# RF_Module_ASK_Transfer.net
KiCad netlist of a schematic drawn in Altium Designer
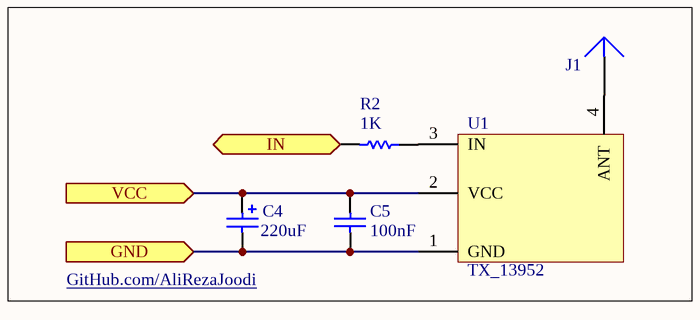
[diagram p0: RF Module_ASK_Transfer.SchDoc]

(export (version "E")
  (design (tool "Eeschema 10.0.6"))
  (components
    (comp (ref "C4")
      (value "220uF")
      (footprint "CAPPR3.05-3.81x6.35")
      (description "Polarized Capacitor (Radial)")
      (fields (field (name "MANUFACTURER") "Generic Components") (field (name "PUBLISHER") "Altium Limited"))
      (libsource (lib "Miscellaneous Devices") (part "Cap Pol1"))
    )
    (comp (ref "C5")
      (value "100nF")
      (footprint "CAPNTO2.54-3.05x1.78A")
      (description "Capacitor")
      (fields (field (name "MANUFACTURER") "Generic Components") (field (name "PUBLISHER") "Altium Limited"))
      (libsource (lib "Miscellaneous Devices") (part "Cap"))
    )
    (comp (ref "J1")
      (value "COAX-M")
      (footprint "PIN1")
      (description "Coax-M Connector")
      (fields (field (name "MANUFACTURER") "Generic Components") (field (name "PUBLISHER") "Altium Limited"))
      (libsource (lib "Miscellaneous Connectors") (part "COAX-M"))
    )
    (comp (ref "R2")
      (value "1K")
      (footprint "AXIAL-0.4")
      (description "Resistor")
      (fields (field (name "PUBLISHER") "Altium Limited"))
      (libsource (lib "Miscellaneous Devices") (part "Res1"))
    )
    (comp (ref "U1")
      (value "TX_13952")
      (footprint "RF_ASK_TX_13952")
      (description "Voltage Regulator")
      (fields (field (name "MANUFACTURER") "Generic Components") (field (name "PUBLISHER") "Altium Limited"))
      (libsource (lib "my Libraries") (part "RF_ASK_TX_13952_2"))
    )
  )
  (nets
    (net (code "1") (name "/GND") (class "Default")
      (node (ref "C4") (pin "2") (pinfunction "2_2") (pintype "passive"))
      (node (ref "C5") (pin "1") (pinfunction "1_1") (pintype "passive"))
      (node (ref "U1") (pin "1") (pinfunction "GND_1") (pintype "passive"))
    )
    (net (code "2") (name "/IN") (class "Default")
      (node (ref "R2") (pin "2") (pinfunction "2_2") (pintype "passive"))
    )
    (net (code "3") (name "/VCC") (class "Default")
      (node (ref "C4") (pin "1") (pinfunction "1_1") (pintype "passive"))
      (node (ref "C5") (pin "2") (pinfunction "2_2") (pintype "passive"))
      (node (ref "U1") (pin "2") (pinfunction "VCC_2") (pintype "passive"))
    )
    (net (code "4") (name "Net-(J1-A)") (class "Default")
      (node (ref "J1") (pin "1") (pinfunction "A_1") (pintype "passive"))
      (node (ref "U1") (pin "4") (pinfunction "ANT_4") (pintype "passive"))
    )
    (net (code "5") (name "Net-(U1-IN)") (class "Default")
      (node (ref "R2") (pin "1") (pinfunction "1_1") (pintype "passive"))
      (node (ref "U1") (pin "3") (pinfunction "IN_3") (pintype "passive"))
    )
  )
)
